# untitled.net
KiCad netlist of a schematic drawn in EAGLE
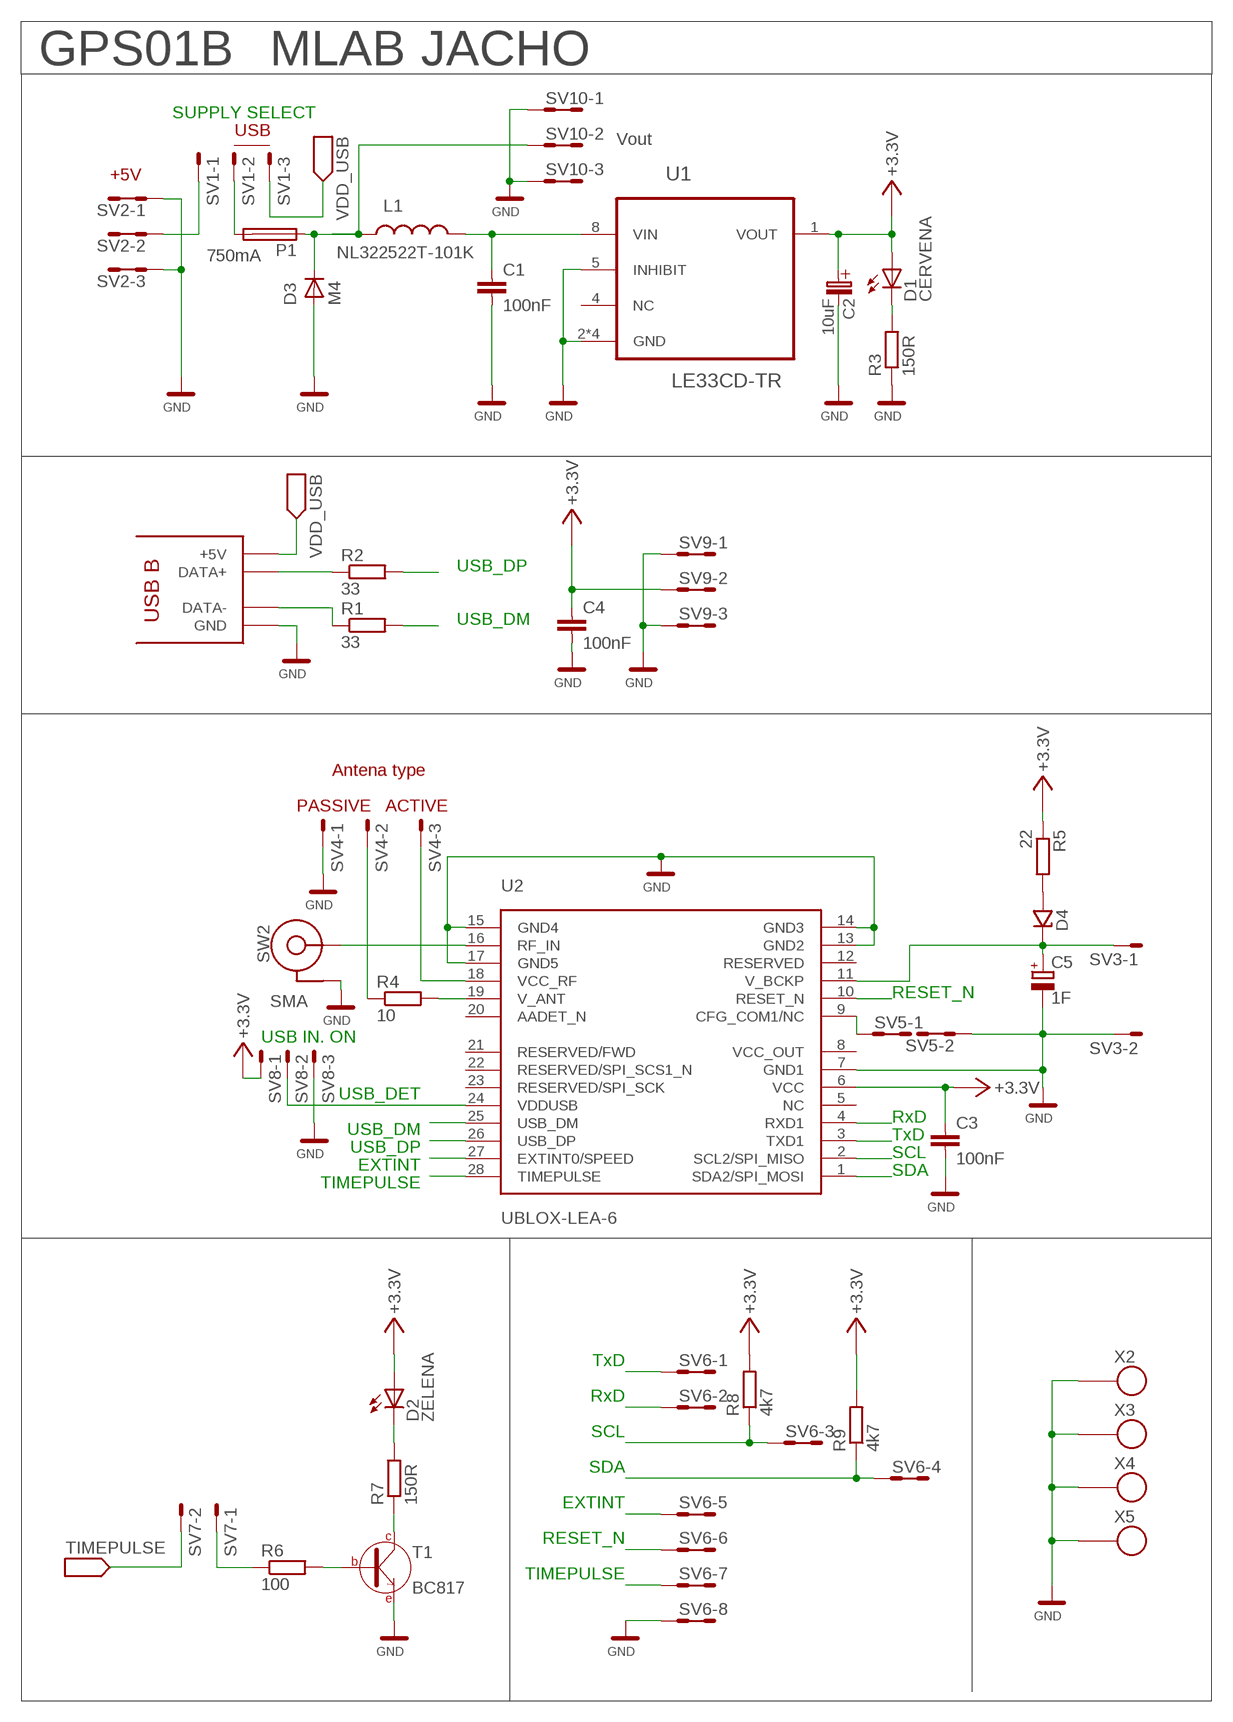
[diagram p0: schematic, sheet 1]

(export (version "E")
  (design (tool "Eeschema 10.0.6"))
  (components
    (comp (ref "C1")
      (value "100nF")
      (footprint "eagle-import:C0805")
      (libsource (lib "eagle-import") (part "C0805"))
    )
    (comp (ref "C2") (value "10uF") (footprint "eagle-import:B") (libsource (lib "eagle-import") (part "B")))
    (comp (ref "C3")
      (value "100nF")
      (footprint "eagle-import:C0805")
      (libsource (lib "eagle-import") (part "C0805"))
    )
    (comp (ref "C4")
      (value "100nF")
      (footprint "eagle-import:C0805")
      (libsource (lib "eagle-import") (part "C0805"))
    )
    (comp (ref "C5")
      (value "1F")
      (footprint "eagle-import:E3,5-8")
      (libsource (lib "eagle-import") (part "CPOL-EUE3.5-8"))
    )
    (comp (ref "D1")
      (value "CERVENA")
      (footprint "eagle-import:1206")
      (libsource (lib "eagle-import") (part "LED1206"))
    )
    (comp (ref "D2")
      (value "ZELENA")
      (footprint "eagle-import:1206")
      (libsource (lib "eagle-import") (part "LED1206"))
    )
    (comp (ref "D3")
      (value "M4")
      (footprint "eagle-import:SMA")
      (libsource (lib "eagle-import") (part "D-OB.SMA"))
    )
    (comp (ref "D4")
      (value "D-ZENEROVA")
      (footprint "eagle-import:MINIMELF")
      (libsource (lib "eagle-import") (part "D-ZENEROVA"))
    )
    (comp (ref "L1")
      (value "NL322522T-101K")
      (footprint "eagle-import:1210")
      (libsource (lib "eagle-import") (part "L1210"))
    )
    (comp (ref "P1")
      (value "750mA")
      (footprint "eagle-import:1812")
      (libsource (lib "eagle-import") (part "POJISTKA_1812"))
    )
    (comp (ref "R1")
      (value "33")
      (footprint "eagle-import:0805")
      (libsource (lib "eagle-import") (part "R0805"))
    )
    (comp (ref "R2")
      (value "33")
      (footprint "eagle-import:0805")
      (libsource (lib "eagle-import") (part "R0805"))
    )
    (comp (ref "R3")
      (value "150R")
      (footprint "eagle-import:0805")
      (libsource (lib "eagle-import") (part "R0805"))
    )
    (comp (ref "R4")
      (value "10")
      (footprint "eagle-import:0805")
      (libsource (lib "eagle-import") (part "R0805"))
    )
    (comp (ref "R5")
      (value "22")
      (footprint "eagle-import:0805")
      (libsource (lib "eagle-import") (part "R0805"))
    )
    (comp (ref "R6")
      (value "100")
      (footprint "eagle-import:0805")
      (libsource (lib "eagle-import") (part "R0805"))
    )
    (comp (ref "R7")
      (value "150R")
      (footprint "eagle-import:0805")
      (libsource (lib "eagle-import") (part "R0805"))
    )
    (comp (ref "R8")
      (value "4k7")
      (footprint "eagle-import:0805")
      (libsource (lib "eagle-import") (part "R0805"))
    )
    (comp (ref "R9")
      (value "4k7")
      (footprint "eagle-import:0805")
      (libsource (lib "eagle-import") (part "R0805"))
    )
    (comp (ref "SV1")
      (value "MA03-1")
      (footprint "eagle-import:MA03-1")
      (libsource (lib "eagle-import") (part "MA03-1"))
    )
    (comp (ref "SV2")
      (value "MA03-2")
      (footprint "eagle-import:MA03-2")
      (libsource (lib "eagle-import") (part "MA03-2"))
    )
    (comp (ref "SV3")
      (value "MA02-1")
      (footprint "eagle-import:MA02-1")
      (libsource (lib "eagle-import") (part "MA02-1"))
    )
    (comp (ref "SV4")
      (value "MA03-1")
      (footprint "eagle-import:MA03-1")
      (libsource (lib "eagle-import") (part "MA03-1"))
    )
    (comp (ref "SV5")
      (value "MA02-2")
      (footprint "eagle-import:MA02-2")
      (libsource (lib "eagle-import") (part "MA02-2"))
    )
    (comp (ref "SV6")
      (value "MA08-2")
      (footprint "eagle-import:MA08-2")
      (libsource (lib "eagle-import") (part "MA08-2"))
    )
    (comp (ref "SV7")
      (value "MA02-1")
      (footprint "eagle-import:MA02-1")
      (libsource (lib "eagle-import") (part "MA02-1"))
    )
    (comp (ref "SV8")
      (value "MA03-1")
      (footprint "eagle-import:MA03-1")
      (libsource (lib "eagle-import") (part "MA03-1"))
    )
    (comp (ref "SV9")
      (value "MA03-2")
      (footprint "eagle-import:MA03-2")
      (libsource (lib "eagle-import") (part "MA03-2"))
    )
    (comp (ref "SV10")
      (value "MA03-2")
      (footprint "eagle-import:MA03-2")
      (libsource (lib "eagle-import") (part "MA03-2"))
    )
    (comp (ref "SW2")
      (value "SMA")
      (footprint "eagle-import:SMA")
      (libsource (lib "eagle-import") (part "SMA"))
    )
    (comp (ref "T1")
      (value "BC817")
      (footprint "eagle-import:SOT23")
      (libsource (lib "eagle-import") (part "BC817"))
    )
    (comp (ref "U1")
      (value "LE33CD-TR")
      (footprint "eagle-import:SOIC127P600X175-8N")
      (libsource (lib "eagle-import") (part "LE33CD-TR"))
    )
    (comp (ref "U2")
      (value "UBLOX-LEA-6")
      (footprint "eagle-import:UBLOX-LEA-6")
      (libsource (lib "eagle-import") (part "UBLOX-LEA-6"))
    )
    (comp (ref "X1")
      (value "USB_B")
      (footprint "eagle-import:USB_B")
      (libsource (lib "eagle-import") (part "USB_B"))
    )
    (comp (ref "X2")
      (value "SROUB3M")
      (footprint "eagle-import:SROUB3M")
      (libsource (lib "eagle-import") (part "SROUB3M"))
    )
    (comp (ref "X3")
      (value "SROUB3M")
      (footprint "eagle-import:SROUB3M")
      (libsource (lib "eagle-import") (part "SROUB3M"))
    )
    (comp (ref "X4")
      (value "SROUB3M")
      (footprint "eagle-import:SROUB3M")
      (libsource (lib "eagle-import") (part "SROUB3M"))
    )
    (comp (ref "X5")
      (value "SROUB3M")
      (footprint "eagle-import:SROUB3M")
      (libsource (lib "eagle-import") (part "SROUB3M"))
    )
  )
  (nets
    (net (code "1") (name "+3.3V") (class "Default")
      (node (ref "C2") (pin "+") (pinfunction "C_EL+_+") (pintype "passive"))
      (node (ref "C3") (pin "1") (pinfunction "1_1") (pintype "passive"))
      (node (ref "C4") (pin "1") (pinfunction "1_1") (pintype "passive"))
      (node (ref "D1") (pin "A") (pinfunction "A_A") (pintype "passive"))
      (node (ref "D2") (pin "A") (pinfunction "A_A") (pintype "passive"))
      (node (ref "R5") (pin "1") (pinfunction "1_1") (pintype "passive"))
      (node (ref "R8") (pin "2") (pinfunction "2_2") (pintype "passive"))
      (node (ref "R9") (pin "2") (pinfunction "2_2") (pintype "passive"))
      (node (ref "SV8") (pin "1") (pinfunction "P$1_1") (pintype "passive"))
      (node (ref "SV9") (pin "3") (pinfunction "K_3") (pintype "passive"))
      (node (ref "SV9") (pin "4") (pinfunction "K_4") (pintype "passive"))
      (node (ref "U1") (pin "1") (pinfunction "VOUT_1") (pintype "output"))
      (node (ref "U2") (pin "6") (pinfunction "VCC_6") (pintype "bidirectional"))
    )
    (net (code "2") (name "/EXTINT") (class "Default")
      (node (ref "SV6") (pin "10") (pinfunction "K_10") (pintype "passive"))
      (node (ref "SV6") (pin "9") (pinfunction "K_9") (pintype "passive"))
      (node (ref "U2") (pin "27") (pinfunction "EXTINT0/SPEED_27") (pintype "bidirectional"))
    )
    (net (code "3") (name "/RESET_N") (class "Default")
      (node (ref "SV6") (pin "11") (pinfunction "K_11") (pintype "passive"))
      (node (ref "SV6") (pin "12") (pinfunction "K_12") (pintype "passive"))
      (node (ref "U2") (pin "10") (pinfunction "RESET_N_10") (pintype "bidirectional"))
    )
    (net (code "4") (name "/RXD") (class "Default")
      (node (ref "SV6") (pin "3") (pinfunction "K_3") (pintype "passive"))
      (node (ref "SV6") (pin "4") (pinfunction "K_4") (pintype "passive"))
      (node (ref "U2") (pin "4") (pinfunction "RXD1_4") (pintype "bidirectional"))
    )
    (net (code "5") (name "/SCL") (class "Default")
      (node (ref "R8") (pin "1") (pinfunction "1_1") (pintype "passive"))
      (node (ref "SV6") (pin "5") (pinfunction "K_5") (pintype "passive"))
      (node (ref "SV6") (pin "6") (pinfunction "K_6") (pintype "passive"))
      (node (ref "U2") (pin "2") (pinfunction "SCL2/SPI_MISO_2") (pintype "bidirectional"))
    )
    (net (code "6") (name "/SDA") (class "Default")
      (node (ref "R9") (pin "1") (pinfunction "1_1") (pintype "passive"))
      (node (ref "SV6") (pin "7") (pinfunction "K_7") (pintype "passive"))
      (node (ref "SV6") (pin "8") (pinfunction "K_8") (pintype "passive"))
      (node (ref "U2") (pin "1") (pinfunction "SDA2/SPI_MOSI_1") (pintype "bidirectional"))
    )
    (net (code "7") (name "/TIMEPULSE") (class "Default")
      (node (ref "SV6") (pin "13") (pinfunction "K_13") (pintype "passive"))
      (node (ref "SV6") (pin "14") (pinfunction "K_14") (pintype "passive"))
      (node (ref "SV7") (pin "2") (pinfunction "P$1_2") (pintype "passive"))
      (node (ref "U2") (pin "28") (pinfunction "TIMEPULSE_28") (pintype "bidirectional"))
    )
    (net (code "8") (name "/TXD") (class "Default")
      (node (ref "SV6") (pin "1") (pinfunction "K_1") (pintype "passive"))
      (node (ref "SV6") (pin "2") (pinfunction "K_2") (pintype "passive"))
      (node (ref "U2") (pin "3") (pinfunction "TXD1_3") (pintype "bidirectional"))
    )
    (net (code "9") (name "/USB_DM") (class "Default")
      (node (ref "R1") (pin "2") (pinfunction "2_2") (pintype "passive"))
      (node (ref "U2") (pin "25") (pinfunction "USB_DM_25") (pintype "bidirectional"))
    )
    (net (code "10") (name "/USB_DP") (class "Default")
      (node (ref "R2") (pin "2") (pinfunction "2_2") (pintype "passive"))
      (node (ref "U2") (pin "26") (pinfunction "USB_DP_26") (pintype "bidirectional"))
    )
    (net (code "11") (name "/VDD_USB") (class "Default")
      (node (ref "SV1") (pin "3") (pinfunction "P$1_3") (pintype "passive"))
      (node (ref "X1") (pin "1") (pinfunction "+5V_1") (pintype "bidirectional"))
    )
    (net (code "12") (name "GND") (class "Default")
      (node (ref "C1") (pin "2") (pinfunction "2_2") (pintype "passive"))
      (node (ref "C2") (pin "-") (pinfunction "C_EL-_-") (pintype "passive"))
      (node (ref "C3") (pin "2") (pinfunction "2_2") (pintype "passive"))
      (node (ref "C4") (pin "2") (pinfunction "2_2") (pintype "passive"))
      (node (ref "C5") (pin "-") (pinfunction "-_-") (pintype "passive"))
      (node (ref "D3") (pin "A") (pinfunction "A_A") (pintype "passive"))
      (node (ref "R3") (pin "1") (pinfunction "1_1") (pintype "passive"))
      (node (ref "SV10") (pin "1") (pinfunction "K_1") (pintype "passive"))
      (node (ref "SV10") (pin "2") (pinfunction "K_2") (pintype "passive"))
      (node (ref "SV10") (pin "5") (pinfunction "K_5") (pintype "passive"))
      (node (ref "SV10") (pin "6") (pinfunction "K_6") (pintype "passive"))
      (node (ref "SV2") (pin "1") (pinfunction "K_1") (pintype "passive"))
      (node (ref "SV2") (pin "2") (pinfunction "K_2") (pintype "passive"))
      (node (ref "SV2") (pin "5") (pinfunction "K_5") (pintype "passive"))
      (node (ref "SV2") (pin "6") (pinfunction "K_6") (pintype "passive"))
      (node (ref "SV3") (pin "2") (pinfunction "P$1_2") (pintype "passive"))
      (node (ref "SV4") (pin "1") (pinfunction "P$1_1") (pintype "passive"))
      (node (ref "SV5") (pin "3") (pinfunction "K_3") (pintype "passive"))
      (node (ref "SV5") (pin "4") (pinfunction "K_4") (pintype "passive"))
      (node (ref "SV6") (pin "15") (pinfunction "K_15") (pintype "passive"))
      (node (ref "SV6") (pin "16") (pinfunction "K_16") (pintype "passive"))
      (node (ref "SV8") (pin "3") (pinfunction "P$1_3") (pintype "passive"))
      (node (ref "SV9") (pin "1") (pinfunction "K_1") (pintype "passive"))
      (node (ref "SV9") (pin "2") (pinfunction "K_2") (pintype "passive"))
      (node (ref "SV9") (pin "5") (pinfunction "K_5") (pintype "passive"))
      (node (ref "SV9") (pin "6") (pinfunction "K_6") (pintype "passive"))
      (node (ref "SW2") (pin "-1") (pinfunction "-_-1") (pintype "passive"))
      (node (ref "SW2") (pin "-2") (pinfunction "-_-2") (pintype "passive"))
      (node (ref "SW2") (pin "-3") (pinfunction "-_-3") (pintype "passive"))
      (node (ref "SW2") (pin "-4") (pinfunction "-_-4") (pintype "passive"))
      (node (ref "T1") (pin "2") (pinfunction "E_2") (pintype "passive"))
      (node (ref "U1") (pin "2") (pinfunction "GND_2") (pintype "passive"))
      (node (ref "U1") (pin "3") (pinfunction "GND_3") (pintype "passive"))
      (node (ref "U1") (pin "5") (pinfunction "INHIBIT_5") (pintype "passive"))
      (node (ref "U1") (pin "6") (pinfunction "GND_6") (pintype "passive"))
      (node (ref "U1") (pin "7") (pinfunction "GND_7") (pintype "passive"))
      (node (ref "U2") (pin "13") (pinfunction "GND2_13") (pintype "bidirectional"))
      (node (ref "U2") (pin "14") (pinfunction "GND3_14") (pintype "bidirectional"))
      (node (ref "U2") (pin "15") (pinfunction "GND4_15") (pintype "bidirectional"))
      (node (ref "U2") (pin "17") (pinfunction "GND5_17") (pintype "bidirectional"))
      (node (ref "U2") (pin "7") (pinfunction "GND1_7") (pintype "bidirectional"))
      (node (ref "X1") (pin "4") (pinfunction "GND_4") (pintype "bidirectional"))
      (node (ref "X1") (pin "GND") (pinfunction "GND_GND") (pintype "bidirectional"))
      (node (ref "X1") (pin "GND2") (pinfunction "GND_GND2") (pintype "bidirectional"))
      (node (ref "X2") (pin "P$1") (pinfunction "P$1_P$1") (pintype "bidirectional"))
      (node (ref "X3") (pin "P$1") (pinfunction "P$1_P$1") (pintype "bidirectional"))
      (node (ref "X4") (pin "P$1") (pinfunction "P$1_P$1") (pintype "bidirectional"))
      (node (ref "X5") (pin "P$1") (pinfunction "P$1_P$1") (pintype "bidirectional"))
    )
    (net (code "13") (name "Net-(D1-C)") (class "Default")
      (node (ref "D1") (pin "K") (pinfunction "C_K") (pintype "passive"))
      (node (ref "R3") (pin "2") (pinfunction "2_2") (pintype "passive"))
    )
    (net (code "14") (name "Net-(D2-C)") (class "Default")
      (node (ref "D2") (pin "K") (pinfunction "C_K") (pintype "passive"))
      (node (ref "R7") (pin "2") (pinfunction "2_2") (pintype "passive"))
    )
    (net (code "15") (name "Net-(D3-C)") (class "Default")
      (node (ref "D3") (pin "K") (pinfunction "C_K") (pintype "passive"))
      (node (ref "L1") (pin "P$1") (pinfunction "1_P$1") (pintype "passive"))
      (node (ref "P1") (pin "1") (pinfunction "1_1") (pintype "passive"))
      (node (ref "SV10") (pin "3") (pinfunction "K_3") (pintype "passive"))
      (node (ref "SV10") (pin "4") (pinfunction "K_4") (pintype "passive"))
    )
    (net (code "16") (name "Net-(D4-K)") (class "Default")
      (node (ref "C5") (pin "+") (pinfunction "+_+") (pintype "passive"))
      (node (ref "D4") (pin "C") (pinfunction "K_C") (pintype "passive"))
      (node (ref "SV3") (pin "1") (pinfunction "P$1_1") (pintype "passive"))
      (node (ref "U2") (pin "11") (pinfunction "V_BCKP_11") (pintype "bidirectional"))
    )
    (net (code "17") (name "Net-(D4-PadA)") (class "Default")
      (node (ref "D4") (pin "A") (pinfunction "A_A") (pintype "passive"))
      (node (ref "R5") (pin "2") (pinfunction "2_2") (pintype "passive"))
    )
    (net (code "18") (name "Net-(L1-2)") (class "Default")
      (node (ref "C1") (pin "1") (pinfunction "1_1") (pintype "passive"))
      (node (ref "L1") (pin "P$2") (pinfunction "2_P$2") (pintype "passive"))
      (node (ref "U1") (pin "8") (pinfunction "VIN_8") (pintype "power_in"))
    )
    (net (code "19") (name "Net-(SV1A-P$1)") (class "Default")
      (node (ref "SV1") (pin "1") (pinfunction "P$1_1") (pintype "passive"))
      (node (ref "SV2") (pin "3") (pinfunction "K_3") (pintype "passive"))
      (node (ref "SV2") (pin "4") (pinfunction "K_4") (pintype "passive"))
    )
    (net (code "20") (name "Net-(SV1B-P$1)") (class "Default")
      (node (ref "P1") (pin "2") (pinfunction "2_2") (pintype "passive"))
      (node (ref "SV1") (pin "2") (pinfunction "P$1_2") (pintype "passive"))
    )
    (net (code "21") (name "Net-(SV4B-P$1)") (class "Default")
      (node (ref "R4") (pin "1") (pinfunction "1_1") (pintype "passive"))
      (node (ref "SV4") (pin "2") (pinfunction "P$1_2") (pintype "passive"))
    )
    (net (code "22") (name "Net-(SV4C-P$1)") (class "Default")
      (node (ref "SV4") (pin "3") (pinfunction "P$1_3") (pintype "passive"))
      (node (ref "U2") (pin "18") (pinfunction "VCC_RF_18") (pintype "bidirectional"))
    )
    (net (code "23") (name "Net-(SV7A-P$1)") (class "Default")
      (node (ref "R6") (pin "1") (pinfunction "1_1") (pintype "passive"))
      (node (ref "SV7") (pin "1") (pinfunction "P$1_1") (pintype "passive"))
    )
    (net (code "24") (name "Net-(SV8B-P$1)") (class "Default")
      (node (ref "SV8") (pin "2") (pinfunction "P$1_2") (pintype "passive"))
      (node (ref "U2") (pin "24") (pinfunction "VDDUSB_24") (pintype "bidirectional"))
    )
    (net (code "25") (name "Net-(T1-B)") (class "Default")
      (node (ref "R6") (pin "2") (pinfunction "2_2") (pintype "passive"))
      (node (ref "T1") (pin "1") (pinfunction "B_1") (pintype "passive"))
    )
    (net (code "26") (name "Net-(T1-C)") (class "Default")
      (node (ref "R7") (pin "1") (pinfunction "1_1") (pintype "passive"))
      (node (ref "T1") (pin "3") (pinfunction "C_3") (pintype "passive"))
    )
    (net (code "27") (name "Net-(U2-CFG_COM1{slash}NC)") (class "Default")
      (node (ref "SV5") (pin "1") (pinfunction "K_1") (pintype "passive"))
      (node (ref "SV5") (pin "2") (pinfunction "K_2") (pintype "passive"))
      (node (ref "U2") (pin "9") (pinfunction "CFG_COM1/NC_9") (pintype "bidirectional"))
    )
    (net (code "28") (name "Net-(U2-RF_IN)") (class "Default")
      (node (ref "SW2") (pin "+") (pinfunction "+_+") (pintype "passive"))
      (node (ref "U2") (pin "16") (pinfunction "RF_IN_16") (pintype "bidirectional"))
    )
    (net (code "29") (name "Net-(U2-V_ANT)") (class "Default")
      (node (ref "R4") (pin "2") (pinfunction "2_2") (pintype "passive"))
      (node (ref "U2") (pin "19") (pinfunction "V_ANT_19") (pintype "bidirectional"))
    )
    (net (code "30") (name "Net-(X1-DATA+)") (class "Default")
      (node (ref "R2") (pin "1") (pinfunction "1_1") (pintype "passive"))
      (node (ref "X1") (pin "3") (pinfunction "DATA+_3") (pintype "bidirectional"))
    )
    (net (code "31") (name "Net-(X1-DATA-)") (class "Default")
      (node (ref "R1") (pin "1") (pinfunction "1_1") (pintype "passive"))
      (node (ref "X1") (pin "2") (pinfunction "DATA-_2") (pintype "bidirectional"))
    )
    (net (code "32") (name "unconnected-(U1-NC-Pad4)") (class "Default")
      (node (ref "U1") (pin "4") (pinfunction "NC_4") (pintype "no_connect"))
    )
    (net (code "33") (name "unconnected-(U2-AADET_N-Pad20)") (class "Default")
      (node (ref "U2") (pin "20") (pinfunction "AADET_N_20") (pintype "bidirectional"))
    )
    (net (code "34") (name "unconnected-(U2-NC-Pad5)") (class "Default")
      (node (ref "U2") (pin "5") (pinfunction "NC_5") (pintype "bidirectional"))
    )
    (net (code "35") (name "unconnected-(U2-RESERVED-Pad12)") (class "Default")
      (node (ref "U2") (pin "12") (pinfunction "RESERVED_12") (pintype "bidirectional"))
    )
    (net (code "36") (name "unconnected-(U2-RESERVED{slash}FWD-Pad21)") (class "Default")
      (node (ref "U2") (pin "21") (pinfunction "RESERVED/FWD_21") (pintype "bidirectional"))
    )
    (net (code "37") (name "unconnected-(U2-RESERVED{slash}SPI_SCK-Pad23)") (class "Default")
      (node (ref "U2") (pin "23") (pinfunction "RESERVED/SPI_SCK_23") (pintype "bidirectional"))
    )
    (net (code "38") (name "unconnected-(U2-RESERVED{slash}SPI_SCS1_N-Pad22)") (class "Default")
      (node (ref "U2") (pin "22") (pinfunction "RESERVED/SPI_SCS1_N_22") (pintype "bidirectional"))
    )
    (net (code "39") (name "unconnected-(U2-VCC_OUT-Pad8)") (class "Default")
      (node (ref "U2") (pin "8") (pinfunction "VCC_OUT_8") (pintype "bidirectional"))
    )
  )
)
